# Zdroj.net
KiCad netlist of a schematic drawn in Altium Designer
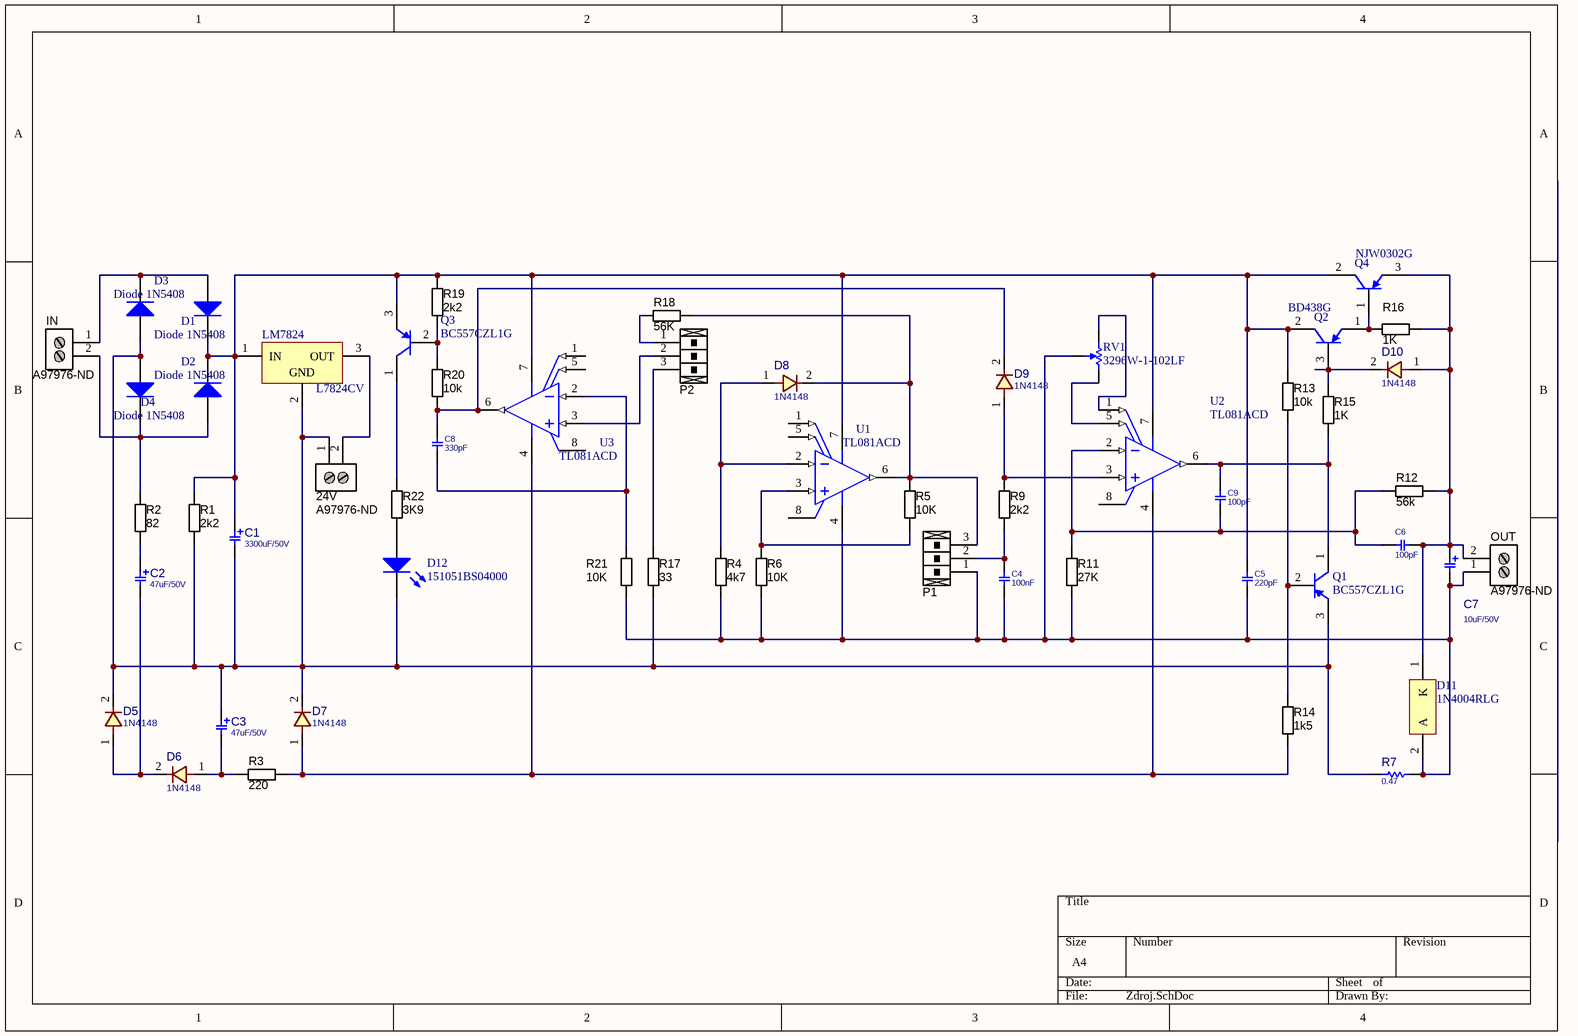
[diagram p0: Zdroj.SchDoc]

(export (version "E")
  (design (tool "Eeschema 10.0.6"))
  (components
    (comp (ref "24V")
      (value "Stackable ScrewTerm")
      (footprint "2P_PCB_ScrewTerm_90S_3.81MM")
      (description "Terminal Block Screw Type THT 2-Position 3.81mm pitch")
      (fields (field (name "SUPPLIER PART NUMBER 1") "A97976-ND"))
      (libsource (lib "") (part "2P_ScrewTerm_90S_3.81MM_1"))
    )
    (comp (ref "C1")
      (value "3300uF/50V")
      (footprint "C_EL_18X35")
      (description "CAP, THD, ELEC,")
      (fields (field (name "MANF_P#") "MANF_PART#") (field (name "MANF") "MANF"))
      (libsource (lib "Passive") (part "CAP_THD_EL"))
    )
    (comp (ref "C2")
      (value "47uF/50V")
      (footprint "C_EL_8X12")
      (description "CAP, THD, ELEC,")
      (fields (field (name "MANF_P#") "MANF_PART#") (field (name "MANF") "MANF"))
      (libsource (lib "Passive") (part "CAP_THD_EL"))
    )
    (comp (ref "C3")
      (value "47uF/50V")
      (footprint "C_EL_8X12")
      (description "CAP, THD, ELEC,")
      (fields (field (name "MANF_P#") "MANF_PART#") (field (name "MANF") "MANF"))
      (libsource (lib "Passive") (part "CAP_THD_EL"))
    )
    (comp (ref "C4")
      (value "100nF")
      (footprint "C_CER_D3")
      (description "CAP, THD, CER MULTI LAYER")
      (fields (field (name "MANF_P#") "MANF_PART#") (field (name "MANF") "MANF"))
      (libsource (lib "Passive") (part "CAP_THD_CERML"))
    )
    (comp (ref "C5")
      (value "220pF")
      (footprint "C_CER_D3")
      (description "CAP, THD, CER MULTI LAYER")
      (fields (field (name "MANF_P#") "MANF_PART#") (field (name "MANF") "MANF"))
      (libsource (lib "Passive") (part "CAP_THD_CERML"))
    )
    (comp (ref "C6")
      (value "100pF")
      (footprint "C_CER_D3")
      (description "CAP, THD, CER MULTI LAYER")
      (fields (field (name "MANF_P#") "MANF_PART#") (field (name "MANF") "MANF"))
      (libsource (lib "Passive") (part "CAP_THD_CERML"))
    )
    (comp (ref "C7")
      (value "10uF/50V")
      (footprint "C_EL_8X12")
      (description "CAP, THD, ELEC,")
      (fields (field (name "MANF_P#") "MANF_PART#") (field (name "MANF") "MANF"))
      (libsource (lib "Passive") (part "CAP_THD_EL"))
    )
    (comp (ref "C8")
      (value "330pF")
      (footprint "C_CER_D3")
      (description "CAP, THD, CER MULTI LAYER,")
      (fields (field (name "MANF_P#") "MANF_PART#") (field (name "MANF") "MANF"))
      (libsource (lib "passive_thd") (part "CAP_THD_CERML"))
    )
    (comp (ref "C9")
      (value "100pF")
      (footprint "C_CER_D3")
      (description "CAP, THD, CER MULTI LAYER")
      (fields (field (name "MANF_P#") "MANF_PART#") (field (name "MANF") "MANF"))
      (libsource (lib "Passive") (part "CAP_THD_CERML"))
    )
    (comp (ref "D1")
      (value "Diode 1N5408")
      (footprint "DO-201AD")
      (description "3 Amp Medium Power Silicon Rectifier Diode")
      (fields (field (name "PUBLISHER") "Altium Limited"))
      (libsource (lib "Miscellaneous Devices") (part "Diode 1N5408"))
    )
    (comp (ref "D2")
      (value "Diode 1N5408")
      (footprint "DO-201AD")
      (description "3 Amp Medium Power Silicon Rectifier Diode")
      (fields (field (name "PUBLISHER") "Altium Limited"))
      (libsource (lib "Miscellaneous Devices") (part "Diode 1N5408"))
    )
    (comp (ref "D3")
      (value "Diode 1N5408")
      (footprint "DO-201AD")
      (description "3 Amp Medium Power Silicon Rectifier Diode")
      (fields (field (name "PUBLISHER") "Altium Limited"))
      (libsource (lib "Miscellaneous Devices") (part "Diode 1N5408"))
    )
    (comp (ref "D4")
      (value "Diode 1N5408")
      (footprint "DO-201AD")
      (description "3 Amp Medium Power Silicon Rectifier Diode")
      (fields (field (name "PUBLISHER") "Altium Limited"))
      (libsource (lib "Miscellaneous Devices") (part "Diode 1N5408"))
    )
    (comp (ref "D5")
      (value "1N4148")
      (footprint "D_AX02_DO35")
      (description "DIODE, FAST SWTICHING, THD")
      (fields (field (name "MANF") "MANF"))
      (libsource (lib "Diode") (part "DIODE_THD_1N4148"))
    )
    (comp (ref "D6")
      (value "1N4148")
      (footprint "D_AX02_DO35")
      (description "DIODE, FAST SWTICHING, THD")
      (fields (field (name "MANF") "MANF"))
      (libsource (lib "Diode") (part "DIODE_THD_1N4148"))
    )
    (comp (ref "D7")
      (value "1N4148")
      (footprint "D_AX02_DO35")
      (description "DIODE, FAST SWTICHING, THD")
      (fields (field (name "MANF") "MANF"))
      (libsource (lib "Diode") (part "DIODE_THD_1N4148"))
    )
    (comp (ref "D8")
      (value "1N4148")
      (footprint "D_AX02_DO35")
      (description "DIODE, FAST SWTICHING, THD")
      (fields (field (name "MANF") "MANF"))
      (libsource (lib "Diode") (part "DIODE_THD_1N4148"))
    )
    (comp (ref "D9")
      (value "1N4148")
      (footprint "D_AX02_DO35")
      (description "DIODE, FAST SWTICHING, THD")
      (fields (field (name "MANF") "MANF"))
      (libsource (lib "Diode") (part "DIODE_THD_1N4148"))
    )
    (comp (ref "D10")
      (value "1N4148")
      (footprint "D_AX02_DO35")
      (description "DIODE, FAST SWTICHING, THD")
      (fields (field (name "MANF") "MANF"))
      (libsource (lib "Diode") (part "DIODE_THD_1N4148"))
    )
    (comp (ref "D11")
      (value "1N4004RLG")
      (footprint "ONSC-AXIAL_LEAD-2-59-10_P")
      (description "Standard Recovery Rectifier, 2-Pin Axial_Lead, Pb-Free, Tape and Reel")
      (fields (field (name "MANUFACTURER") "On Semiconductor"))
      (libsource (lib "Altium Content Vault") (part "ONSC-D-K1A2-2_A"))
    )
    (comp (ref "D12")
      (value "151051BS04000")
      (footprint "Type 5mm")
      (description "THT LED round mono-color color lens, WL-TMRW, Blue")
      (fields (field (name "MANUFACTURER") "Wuerth Elektronik"))
      (libsource (lib "Altium Content Vault") (part "WE-LED_K1A2-2"))
    )
    (comp (ref "IN")
      (value "Stackable ScrewTerm")
      (footprint "2P_PCB_ScrewTerm_90S_3.81MM")
      (description "Terminal Block Screw Type THT 2-Position 3.81mm pitch")
      (fields (field (name "SUPPLIER PART NUMBER 1") "A97976-ND"))
      (libsource (lib "") (part "2P_ScrewTerm_90S_3.81MM_2"))
    )
    (comp (ref "LM7824")
      (value "L7824CV")
      (footprint "TO220")
      (description "Positive Voltage Regulator, 24V, 3-Pin TO-220")
      (libsource (lib "Altium Content Vault") (part "PM-REG-L4940-SIL3"))
    )
    (comp (ref "OUT")
      (value "Stackable ScrewTerm")
      (footprint "2P_PCB_ScrewTerm_90S_3.81MM")
      (description "Terminal Block Screw Type THT 2-Position 3.81mm pitch")
      (fields (field (name "SUPPLIER PART NUMBER 1") "A97976-ND"))
      (libsource (lib "Rutledge_library") (part "2P_ScrewTerm_90S_3.81MM"))
    )
    (comp (ref "P1")
      (value "3P_TERM BLOCK HEADER")
      (footprint "3P_PCB_TERM_BLOCK_HDR")
      (description "Terminal Block THT 3-Position header 3.81mm pitch")
      (fields (field (name "VOLTAGE") "300V"))
      (libsource (lib "Rutledge_library") (part "3P_TERM BLOCK HEADER"))
    )
    (comp (ref "P2")
      (value "3P_TERM BLOCK HEADER")
      (footprint "3P_PCB_TERM_BLOCK_HDR")
      (description "Terminal Block THT 3-Position header 3.81mm pitch")
      (fields (field (name "VOLTAGE") "300V"))
      (libsource (lib "") (part "3P_TERM BLOCK HEADER_1"))
    )
    (comp (ref "Q1")
      (value "BC557CZL1G")
      (footprint "ONSC-TO-92-3-29-11_AM_BL")
      (description "Amplifier Transistor, PNP Silicon, 3-Pin TO-92, Pb-Free, Ammo Box")
      (fields (field (name "MANUFACTURER") "On Semiconductor"))
      (libsource (lib "Altium Content Vault") (part "ONSC-PNP-C1B2E3-3"))
    )
    (comp (ref "Q2")
      (value "BD438G")
      (footprint "ONSC-TO-225-3-77-09")
      (description "Plastic Medium Power Silicon PNP Transistor, 3-Pin TO-225, Pb-Free, Bulk Box")
      (fields (field (name "MANUFACTURER") "On Semiconductor"))
      (libsource (lib "Altium Content Vault") (part "ONSC-PNP-E1C2B3-3"))
    )
    (comp (ref "Q3")
      (value "BC557CZL1G")
      (footprint "ONSC-TO-92-3-29-11_AM_BL")
      (description "Amplifier Transistor, PNP Silicon, 3-Pin TO-92, Pb-Free, Ammo Box")
      (fields (field (name "MANUFACTURER") "On Semiconductor"))
      (libsource (lib "Altium Content Vault") (part "ONSC-PNP-C1B2E3-3"))
    )
    (comp (ref "Q4")
      (value "NJW0302G")
      (footprint "ONSC-TO-3P-3LD-3-340AB-01")
      (description "Complementary PNP Power Bipolar Transistor, 3-Pin TO-3P-3LD, Pb-Free, Tube")
      (fields (field (name "MANUFACTURER") "On Semiconductor"))
      (libsource (lib "Altium Content Vault") (part "ONSC-PNP-B1C2E3-3"))
    )
    (comp (ref "R1")
      (value "2k2")
      (footprint "RESTH_AXIAL-0.4")
      (description "Resistor THD Axial 1k Ohm 0.25W 5% Carbon Film")
      (fields (field (name "TOLERANCE") "±5%") (field (name "Comment") "Carbon Film"))
      (libsource (lib "Rutledge_library") (part "RES_1K_Axial_0.25W_5%"))
    )
    (comp (ref "R2")
      (value "82")
      (footprint "RESTH_AXIAL-0.4")
      (description "Resistor THD Axial 1k Ohm 0.25W 5% Carbon Film")
      (fields (field (name "TOLERANCE") "±5%") (field (name "Comment") "Carbon Film"))
      (libsource (lib "Rutledge_library") (part "RES_1K_Axial_0.25W_5%"))
    )
    (comp (ref "R3")
      (value "220")
      (footprint "RESTH_AXIAL-0.4")
      (description "Resistor THD Axial 1k Ohm 0.25W 5% Carbon Film")
      (fields (field (name "TOLERANCE") "±5%") (field (name "Comment") "Carbon Film"))
      (libsource (lib "") (part "RES_1K_Axial_0.25W_5%_2"))
    )
    (comp (ref "R4")
      (value "4k7")
      (footprint "RESTH_AXIAL-0.4")
      (description "Resistor THD Axial 1k Ohm 0.25W 5% Carbon Film")
      (fields (field (name "TOLERANCE") "±5%") (field (name "Comment") "Carbon Film"))
      (libsource (lib "Rutledge_library") (part "RES_1K_Axial_0.25W_5%"))
    )
    (comp (ref "R5")
      (value "10K")
      (footprint "RESTH_AXIAL-0.4")
      (description "Resistor THD Axial 1k Ohm 0.25W 5% Carbon Film")
      (fields (field (name "TOLERANCE") "±5%") (field (name "Comment") "Carbon Film"))
      (libsource (lib "") (part "RES_1K_Axial_0.25W_5%_1"))
    )
    (comp (ref "R6")
      (value "10K")
      (footprint "RESTH_AXIAL-0.4")
      (description "Resistor THD Axial 1k Ohm 0.25W 5% Carbon Film")
      (fields (field (name "TOLERANCE") "±5%") (field (name "Comment") "Carbon Film"))
      (libsource (lib "Rutledge_library") (part "RES_1K_Axial_0.25W_5%"))
    )
    (comp (ref "R7")
      (value "0.47")
      (footprint "RWW5W")
      (description "RES, THD")
      (fields (field (name "MANF_P#") "RK73H1ETTP4701F") (field (name "MANF") "KOA SPEER"))
      (libsource (lib "Passive") (part "RES_THD"))
    )
    (comp (ref "R9")
      (value "2k2")
      (footprint "RESTH_AXIAL-0.4")
      (description "Resistor THD Axial 1k Ohm 0.25W 5% Carbon Film")
      (fields (field (name "TOLERANCE") "±5%") (field (name "Comment") "Carbon Film"))
      (libsource (lib "Rutledge_library") (part "RES_1K_Axial_0.25W_5%"))
    )
    (comp (ref "R11")
      (value "27K")
      (footprint "RESTH_AXIAL-0.4")
      (description "Resistor THD Axial 1k Ohm 0.25W 5% Carbon Film")
      (fields (field (name "TOLERANCE") "±5%") (field (name "Comment") "Carbon Film"))
      (libsource (lib "Rutledge_library") (part "RES_1K_Axial_0.25W_5%"))
    )
    (comp (ref "R12")
      (value "56k")
      (footprint "RESTH_AXIAL-0.4")
      (description "Resistor THD Axial 1k Ohm 0.25W 5% Carbon Film")
      (fields (field (name "TOLERANCE") "±5%") (field (name "Comment") "Carbon Film"))
      (libsource (lib "") (part "RES_1K_Axial_0.25W_5%_2"))
    )
    (comp (ref "R13")
      (value "10k")
      (footprint "RESTH_AXIAL-0.4")
      (description "Resistor THD Axial 1k Ohm 0.25W 5% Carbon Film")
      (fields (field (name "TOLERANCE") "±5%") (field (name "Comment") "Carbon Film"))
      (libsource (lib "Rutledge_library") (part "RES_1K_Axial_0.25W_5%"))
    )
    (comp (ref "R14")
      (value "1k5")
      (footprint "RESTH_AXIAL-0.4")
      (description "Resistor THD Axial 1k Ohm 0.25W 5% Carbon Film")
      (fields (field (name "TOLERANCE") "±5%") (field (name "Comment") "Carbon Film"))
      (libsource (lib "Rutledge_library") (part "RES_1K_Axial_0.25W_5%"))
    )
    (comp (ref "R15")
      (value "1K")
      (footprint "RESTH_AXIAL-0.4")
      (description "Resistor THD Axial 1k Ohm 0.25W 5% Carbon Film")
      (fields (field (name "TOLERANCE") "±5%") (field (name "Comment") "Carbon Film"))
      (libsource (lib "Rutledge_library") (part "RES_1K_Axial_0.25W_5%"))
    )
    (comp (ref "R16")
      (value "1K")
      (footprint "RESTH_AXIAL-0.4")
      (description "Resistor THD Axial 1k Ohm 0.25W 5% Carbon Film")
      (fields (field (name "TOLERANCE") "±5%") (field (name "Comment") "Carbon Film"))
      (libsource (lib "") (part "RES_1K_Axial_0.25W_5%_2"))
    )
    (comp (ref "R17")
      (value "33")
      (footprint "RESTH_AXIAL-0.4")
      (description "Resistor THD Axial 1k Ohm 0.25W 5% Carbon Film")
      (fields (field (name "TOLERANCE") "±5%") (field (name "Comment") "Carbon Film"))
      (libsource (lib "Rutledge_library") (part "RES_1K_Axial_0.25W_5%"))
    )
    (comp (ref "R18")
      (value "56K")
      (footprint "RESTH_AXIAL-0.4")
      (description "Resistor THD Axial 1k Ohm 0.25W 5% Carbon Film")
      (fields (field (name "TOLERANCE") "±5%") (field (name "Comment") "Carbon Film"))
      (libsource (lib "") (part "RES_1K_Axial_0.25W_5%_2"))
    )
    (comp (ref "R19")
      (value "2k2")
      (footprint "RESTH_AXIAL-0.4")
      (description "Resistor THD Axial 1k Ohm 0.25W 5% Carbon Film")
      (fields (field (name "TOLERANCE") "±5%") (field (name "Comment") "Carbon Film"))
      (libsource (lib "Rutledge_library") (part "RES_1K_Axial_0.25W_5%"))
    )
    (comp (ref "R20")
      (value "10k")
      (footprint "RESTH_AXIAL-0.4")
      (description "Resistor THD Axial 1k Ohm 0.25W 5% Carbon Film")
      (fields (field (name "TOLERANCE") "±5%") (field (name "Comment") "Carbon Film"))
      (libsource (lib "Rutledge_library") (part "RES_1K_Axial_0.25W_5%"))
    )
    (comp (ref "R21")
      (value "10K")
      (footprint "RESTH_AXIAL-0.4")
      (description "Resistor THD Axial 1k Ohm 0.25W 5% Carbon Film")
      (fields (field (name "TOLERANCE") "±5%") (field (name "Comment") "Carbon Film"))
      (libsource (lib "Rutledge_library") (part "RES_1K_Axial_0.25W_5%"))
    )
    (comp (ref "R22")
      (value "3K9")
      (footprint "RESTH_AXIAL-0.4")
      (description "Resistor THD Axial 1k Ohm 0.25W 5% Carbon Film")
      (fields (field (name "TOLERANCE") "±5%") (field (name "Comment") "Carbon Film"))
      (libsource (lib "Rutledge_library") (part "RES_1K_Axial_0.25W_5%"))
    )
    (comp (ref "RV1")
      (value "3296W-1-102LF")
      (footprint "BOUR-3296W-1-3")
      (description "Square Trimpot(R) Trimming Potentiometer, 1000 Ohm, -55 to 125 degC, 3-Pin THD, RoHS, Tube")
      (fields (field (name "TOLERANCE") "1%"))
      (libsource (lib "Altium Content Vault") (part "RES-ADJ-3"))
    )
    (comp (ref "U1")
      (value "TL081ACD")
      (footprint "D0008A_M")
      (fields (field (name "MANUFACTURER") "Texas Instruments"))
      (libsource (lib "Altium Content Vault") (part "TI-AMP-S5-2-8"))
    )
    (comp (ref "U2")
      (value "TL081ACD")
      (footprint "D0008A_M")
      (fields (field (name "MANUFACTURER") "Texas Instruments"))
      (libsource (lib "Altium Content Vault") (part "TI-AMP-S5-2-8"))
    )
    (comp (ref "U3")
      (value "TL081ACD")
      (footprint "D0008A_M")
      (fields (field (name "MANUFACTURER") "Texas Instruments"))
      (libsource (lib "Altium Content Vault") (part "TI-AMP-S5-2-8"))
    )
  )
  (nets
    (net (code "1") (name "Net-(C2-Pad1)") (class "Default")
      (node (ref "C2") (pin "1") (pinfunction "1_1") (pintype "passive"))
      (node (ref "R2") (pin "2") (pinfunction "2_2") (pintype "passive"))
    )
    (net (code "2") (name "Net-(C2-Pad2)") (class "Default")
      (node (ref "C2") (pin "2") (pinfunction "2_2") (pintype "passive"))
      (node (ref "D5") (pin "1") (pinfunction "1_1") (pintype "passive"))
      (node (ref "D6") (pin "2") (pinfunction "2_2") (pintype "passive"))
    )
    (net (code "3") (name "Net-(C3-Pad2)") (class "Default")
      (node (ref "C3") (pin "2") (pinfunction "2_2") (pintype "passive"))
      (node (ref "D6") (pin "1") (pinfunction "1_1") (pintype "passive"))
      (node (ref "R3") (pin "1") (pinfunction "1_1") (pintype "passive"))
    )
    (net (code "4") (name "Net-(C4-Pad2)") (class "Default")
      (node (ref "C4") (pin "2") (pinfunction "2_2") (pintype "passive"))
      (node (ref "P1") (pin "2") (pinfunction "2_2") (pintype "passive"))
      (node (ref "R9") (pin "2") (pinfunction "2_2") (pintype "passive"))
    )
    (net (code "5") (name "Net-(D1-A)") (class "Default")
      (node (ref "D1") (pin "1") (pinfunction "A_1") (pintype "passive"))
      (node (ref "D3") (pin "2") (pinfunction "K_2") (pintype "passive"))
      (node (ref "IN") (pin "1") (pinfunction "1_1") (pintype "passive"))
    )
    (net (code "6") (name "Net-(D1-K)") (class "Default")
      (node (ref "C1") (pin "1") (pinfunction "1_1") (pintype "passive"))
      (node (ref "C5") (pin "2") (pinfunction "2_2") (pintype "passive"))
      (node (ref "D1") (pin "2") (pinfunction "K_2") (pintype "passive"))
      (node (ref "D2") (pin "2") (pinfunction "K_2") (pintype "passive"))
      (node (ref "LM7824") (pin "1") (pinfunction "IN_1") (pintype "power_in"))
      (node (ref "Q2") (pin "2") (pinfunction "C_2") (pintype "passive"))
      (node (ref "Q3") (pin "3") (pinfunction "E_3") (pintype "passive"))
      (node (ref "Q4") (pin "2") (pinfunction "C_2") (pintype "passive"))
      (node (ref "R1") (pin "1") (pinfunction "1_1") (pintype "passive"))
      (node (ref "R13") (pin "1") (pinfunction "1_1") (pintype "passive"))
      (node (ref "R19") (pin "1") (pinfunction "1_1") (pintype "passive"))
      (node (ref "U1") (pin "7") (pinfunction "VCC+_7") (pintype "power_in"))
      (node (ref "U2") (pin "7") (pinfunction "VCC+_7") (pintype "power_in"))
      (node (ref "U3") (pin "7") (pinfunction "VCC+_7") (pintype "power_in"))
    )
    (net (code "7") (name "Net-(D2-A)") (class "Default")
      (node (ref "D2") (pin "1") (pinfunction "A_1") (pintype "passive"))
      (node (ref "D4") (pin "2") (pinfunction "K_2") (pintype "passive"))
      (node (ref "IN") (pin "2") (pinfunction "2_2") (pintype "passive"))
      (node (ref "R2") (pin "1") (pinfunction "1_1") (pintype "passive"))
    )
    (net (code "8") (name "Net-(D11-A)") (class "Default")
      (node (ref "C4") (pin "1") (pinfunction "1_1") (pintype "passive"))
      (node (ref "C5") (pin "1") (pinfunction "1_1") (pintype "passive"))
      (node (ref "C7") (pin "2") (pinfunction "2_2") (pintype "passive"))
      (node (ref "D11") (pin "2") (pinfunction "A_2") (pintype "passive"))
      (node (ref "OUT") (pin "1") (pinfunction "1_1") (pintype "passive"))
      (node (ref "P1") (pin "1") (pinfunction "1_1") (pintype "passive"))
      (node (ref "R11") (pin "2") (pinfunction "2_2") (pintype "passive"))
      (node (ref "R21") (pin "2") (pinfunction "2_2") (pintype "passive"))
      (node (ref "R4") (pin "2") (pinfunction "2_2") (pintype "passive"))
      (node (ref "R6") (pin "2") (pinfunction "2_2") (pintype "passive"))
      (node (ref "R7") (pin "2") (pinfunction "2_2") (pintype "passive"))
      (node (ref "RV1") (pin "3") (pinfunction "TAP_3") (pintype "passive"))
      (node (ref "U1") (pin "4") (pinfunction "VCC-_4") (pintype "power_in"))
    )
    (net (code "9") (name "Net-(D11-K)") (class "Default")
      (node (ref "C6") (pin "1") (pinfunction "1_1") (pintype "passive"))
      (node (ref "C7") (pin "1") (pinfunction "1_1") (pintype "passive"))
      (node (ref "D10") (pin "1") (pinfunction "1_1") (pintype "passive"))
      (node (ref "D11") (pin "1") (pinfunction "K_1") (pintype "passive"))
      (node (ref "OUT") (pin "2") (pinfunction "2_2") (pintype "passive"))
      (node (ref "Q4") (pin "3") (pinfunction "E_3") (pintype "passive"))
      (node (ref "R12") (pin "2") (pinfunction "2_2") (pintype "passive"))
      (node (ref "R16") (pin "2") (pinfunction "2_2") (pintype "passive"))
    )
    (net (code "10") (name "Net-(D12-A)") (class "Default")
      (node (ref "D12") (pin "2") (pinfunction "A_2") (pintype "passive"))
      (node (ref "R22") (pin "2") (pinfunction "2_2") (pintype "passive"))
    )
    (net (code "11") (name "Net-(D12-K)") (class "Default")
      (node (ref "24V") (pin "1") (pinfunction "1_1") (pintype "passive"))
      (node (ref "C1") (pin "2") (pinfunction "2_2") (pintype "passive"))
      (node (ref "C3") (pin "1") (pinfunction "1_1") (pintype "passive"))
      (node (ref "D12") (pin "1") (pinfunction "K_1") (pintype "passive"))
      (node (ref "D3") (pin "1") (pinfunction "A_1") (pintype "passive"))
      (node (ref "D4") (pin "1") (pinfunction "A_1") (pintype "passive"))
      (node (ref "D5") (pin "2") (pinfunction "2_2") (pintype "passive"))
      (node (ref "D7") (pin "2") (pinfunction "2_2") (pintype "passive"))
      (node (ref "LM7824") (pin "2") (pinfunction "GND_2") (pintype "power_in"))
      (node (ref "Q1") (pin "3") (pinfunction "E_3") (pintype "passive"))
      (node (ref "R1") (pin "2") (pinfunction "2_2") (pintype "passive"))
      (node (ref "R17") (pin "2") (pinfunction "2_2") (pintype "passive"))
      (node (ref "R7") (pin "1") (pinfunction "1_1") (pintype "passive"))
    )
    (net (code "12") (name "Net-(LM7824-OUT)") (class "Default")
      (node (ref "24V") (pin "2") (pinfunction "2_2") (pintype "passive"))
      (node (ref "LM7824") (pin "3") (pinfunction "OUT_3") (pintype "power_in"))
    )
    (net (code "13") (name "Net-(P2-Pad1)") (class "Default")
      (node (ref "P2") (pin "1") (pinfunction "1_1") (pintype "passive"))
      (node (ref "R18") (pin "1") (pinfunction "1_1") (pintype "passive"))
    )
    (net (code "14") (name "Net-(P2-Pad3)") (class "Default")
      (node (ref "P2") (pin "3") (pinfunction "3_3") (pintype "passive"))
      (node (ref "R17") (pin "1") (pinfunction "1_1") (pintype "passive"))
    )
    (net (code "15") (name "Net-(Q1-B)") (class "Default")
      (node (ref "Q1") (pin "2") (pinfunction "B_2") (pintype "passive"))
      (node (ref "R13") (pin "2") (pinfunction "2_2") (pintype "passive"))
      (node (ref "R14") (pin "1") (pinfunction "1_1") (pintype "passive"))
    )
    (net (code "16") (name "Net-(Q1-C)") (class "Default")
      (node (ref "C9") (pin "2") (pinfunction "2_2") (pintype "passive"))
      (node (ref "Q1") (pin "1") (pinfunction "C_1") (pintype "passive"))
      (node (ref "R15") (pin "2") (pinfunction "2_2") (pintype "passive"))
      (node (ref "U2") (pin "6") (pinfunction "OUT_6") (pintype "output"))
    )
    (net (code "17") (name "Net-(Q2-B)") (class "Default")
      (node (ref "D10") (pin "2") (pinfunction "2_2") (pintype "passive"))
      (node (ref "Q2") (pin "3") (pinfunction "B_3") (pintype "passive"))
      (node (ref "R15") (pin "1") (pinfunction "1_1") (pintype "passive"))
    )
    (net (code "18") (name "Net-(Q2-E)") (class "Default")
      (node (ref "Q2") (pin "1") (pinfunction "E_1") (pintype "passive"))
      (node (ref "Q4") (pin "1") (pinfunction "B_1") (pintype "passive"))
      (node (ref "R16") (pin "1") (pinfunction "1_1") (pintype "passive"))
    )
    (net (code "19") (name "Net-(Q3-B)") (class "Default")
      (node (ref "Q3") (pin "2") (pinfunction "B_2") (pintype "passive"))
      (node (ref "R19") (pin "2") (pinfunction "2_2") (pintype "passive"))
      (node (ref "R20") (pin "1") (pinfunction "1_1") (pintype "passive"))
    )
    (net (code "20") (name "Net-(Q3-C)") (class "Default")
      (node (ref "Q3") (pin "1") (pinfunction "C_1") (pintype "passive"))
      (node (ref "R22") (pin "1") (pinfunction "1_1") (pintype "passive"))
    )
    (net (code "21") (name "Net-(RV1-A)") (class "Default")
      (node (ref "RV1") (pin "1") (pinfunction "A_1") (pintype "passive"))
      (node (ref "U2") (pin "1") (pinfunction "OFFSET_N1_1") (pintype "input"))
    )
    (net (code "22") (name "Net-(RV1-B)") (class "Default")
      (node (ref "RV1") (pin "2") (pinfunction "B_2") (pintype "passive"))
      (node (ref "U2") (pin "5") (pinfunction "OFFSET_N2_5") (pintype "input"))
    )
    (net (code "23") (name "Net-(U1-IN+)") (class "Default")
      (node (ref "R5") (pin "1") (pinfunction "1_1") (pintype "passive"))
      (node (ref "R6") (pin "1") (pinfunction "1_1") (pintype "passive"))
      (node (ref "U1") (pin "3") (pinfunction "IN+_3") (pintype "input"))
    )
    (net (code "24") (name "Net-(U1-IN-)") (class "Default")
      (node (ref "D8") (pin "1") (pinfunction "1_1") (pintype "passive"))
      (node (ref "R4") (pin "1") (pinfunction "1_1") (pintype "passive"))
      (node (ref "U1") (pin "2") (pinfunction "IN-_2") (pintype "input"))
    )
    (net (code "25") (name "Net-(U1-OUT)") (class "Default")
      (node (ref "D8") (pin "2") (pinfunction "2_2") (pintype "passive"))
      (node (ref "P1") (pin "3") (pinfunction "3_3") (pintype "passive"))
      (node (ref "R18") (pin "2") (pinfunction "2_2") (pintype "passive"))
      (node (ref "R5") (pin "2") (pinfunction "2_2") (pintype "passive"))
      (node (ref "U1") (pin "6") (pinfunction "OUT_6") (pintype "output"))
    )
    (net (code "26") (name "Net-(U2-IN+)") (class "Default")
      (node (ref "D9") (pin "1") (pinfunction "1_1") (pintype "passive"))
      (node (ref "R9") (pin "1") (pinfunction "1_1") (pintype "passive"))
      (node (ref "U2") (pin "3") (pinfunction "IN+_3") (pintype "input"))
    )
    (net (code "27") (name "Net-(U2-IN-)") (class "Default")
      (node (ref "C6") (pin "2") (pinfunction "2_2") (pintype "passive"))
      (node (ref "C9") (pin "1") (pinfunction "1_1") (pintype "passive"))
      (node (ref "R11") (pin "1") (pinfunction "1_1") (pintype "passive"))
      (node (ref "R12") (pin "1") (pinfunction "1_1") (pintype "passive"))
      (node (ref "U2") (pin "2") (pinfunction "IN-_2") (pintype "input"))
    )
    (net (code "28") (name "Net-(U2-VCC-)") (class "Default")
      (node (ref "D7") (pin "1") (pinfunction "1_1") (pintype "passive"))
      (node (ref "R14") (pin "2") (pinfunction "2_2") (pintype "passive"))
      (node (ref "R3") (pin "2") (pinfunction "2_2") (pintype "passive"))
      (node (ref "U2") (pin "4") (pinfunction "VCC-_4") (pintype "power_in"))
      (node (ref "U3") (pin "4") (pinfunction "VCC-_4") (pintype "power_in"))
    )
    (net (code "29") (name "Net-(U3-IN+)") (class "Default")
      (node (ref "P2") (pin "2") (pinfunction "2_2") (pintype "passive"))
      (node (ref "U3") (pin "3") (pinfunction "IN+_3") (pintype "input"))
    )
    (net (code "30") (name "Net-(U3-IN-)") (class "Default")
      (node (ref "C8") (pin "1") (pinfunction "1_1") (pintype "passive"))
      (node (ref "R21") (pin "1") (pinfunction "1_1") (pintype "passive"))
      (node (ref "U3") (pin "2") (pinfunction "IN-_2") (pintype "input"))
    )
    (net (code "31") (name "Net-(U3-OUT)") (class "Default")
      (node (ref "C8") (pin "2") (pinfunction "2_2") (pintype "passive"))
      (node (ref "D9") (pin "2") (pinfunction "2_2") (pintype "passive"))
      (node (ref "R20") (pin "2") (pinfunction "2_2") (pintype "passive"))
      (node (ref "U3") (pin "6") (pinfunction "OUT_6") (pintype "output"))
    )
    (net (code "32") (name "unconnected-(U1-NC-Pad8)") (class "Default")
      (node (ref "U1") (pin "8") (pinfunction "NC_8") (pintype "passive"))
    )
    (net (code "33") (name "unconnected-(U1-OFFSET_N1-Pad1)") (class "Default")
      (node (ref "U1") (pin "1") (pinfunction "OFFSET_N1_1") (pintype "input"))
    )
    (net (code "34") (name "unconnected-(U1-OFFSET_N2-Pad5)") (class "Default")
      (node (ref "U1") (pin "5") (pinfunction "OFFSET_N2_5") (pintype "input"))
    )
    (net (code "35") (name "unconnected-(U2-NC-Pad8)") (class "Default")
      (node (ref "U2") (pin "8") (pinfunction "NC_8") (pintype "passive"))
    )
    (net (code "36") (name "unconnected-(U3-NC-Pad8)") (class "Default")
      (node (ref "U3") (pin "8") (pinfunction "NC_8") (pintype "passive"))
    )
    (net (code "37") (name "unconnected-(U3-OFFSET_N1-Pad1)") (class "Default")
      (node (ref "U3") (pin "1") (pinfunction "OFFSET_N1_1") (pintype "input"))
    )
    (net (code "38") (name "unconnected-(U3-OFFSET_N2-Pad5)") (class "Default")
      (node (ref "U3") (pin "5") (pinfunction "OFFSET_N2_5") (pintype "input"))
    )
  )
)
